# mcu.net
KiCad netlist of a schematic drawn in Altium Designer
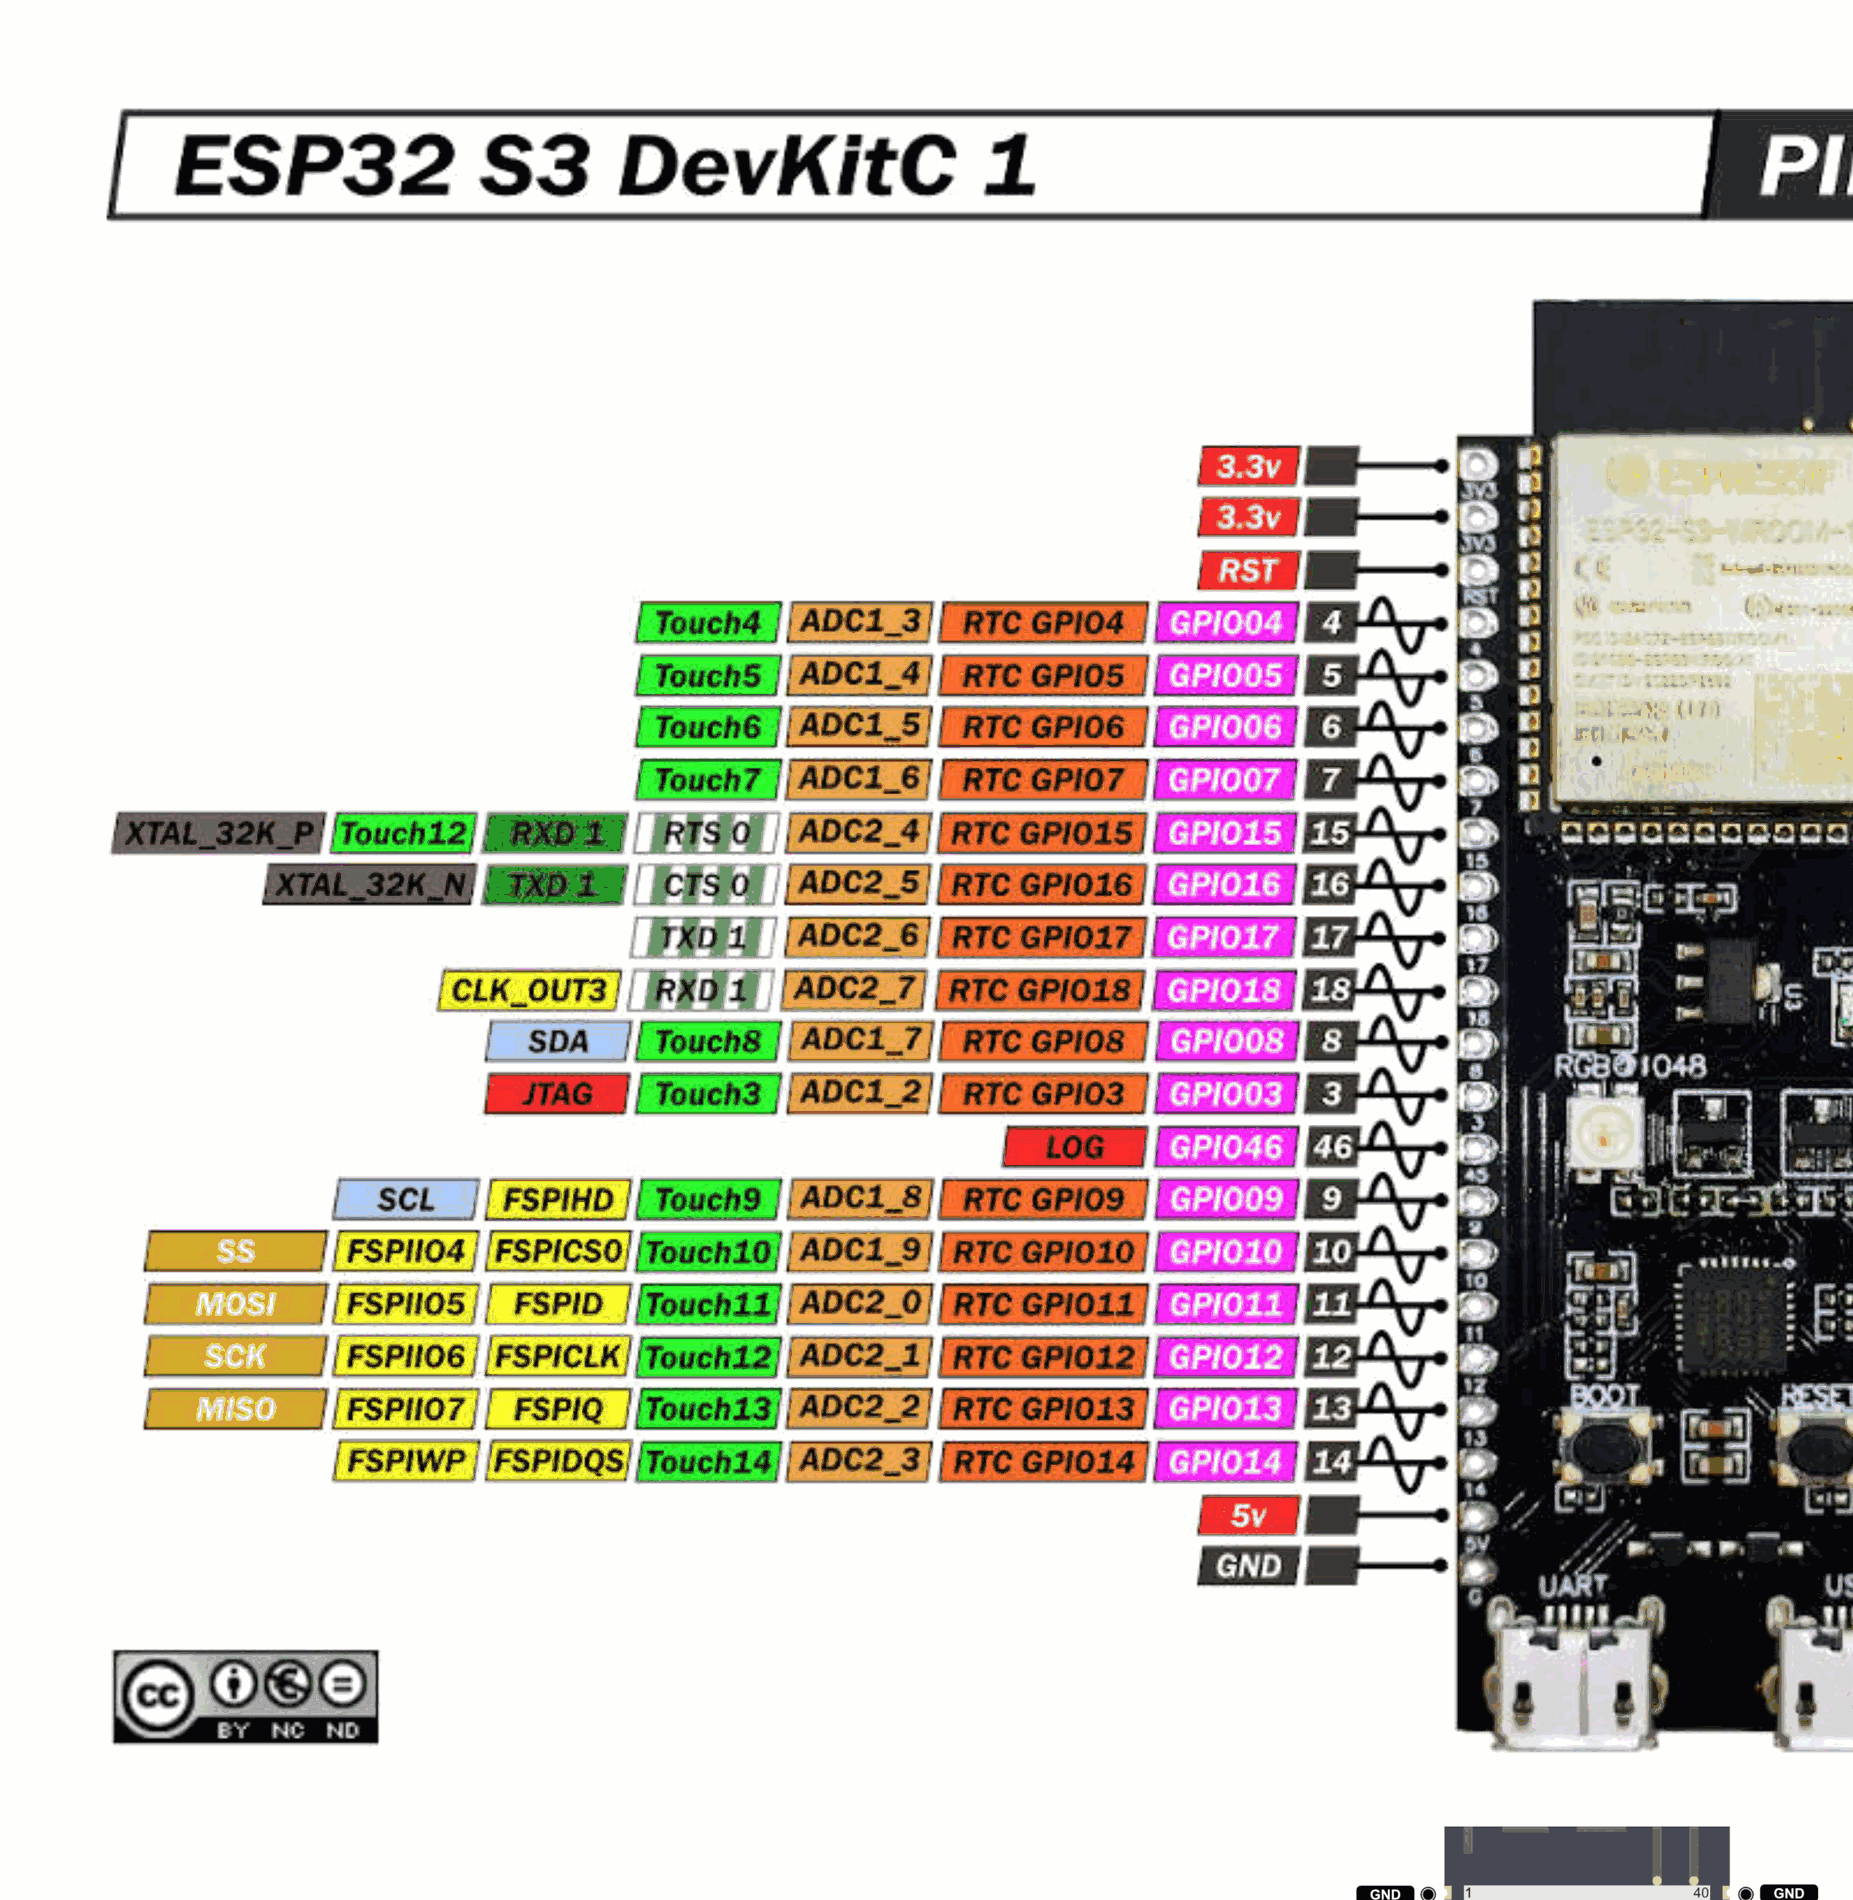
[diagram p0: mcu.SchDoc, top left]
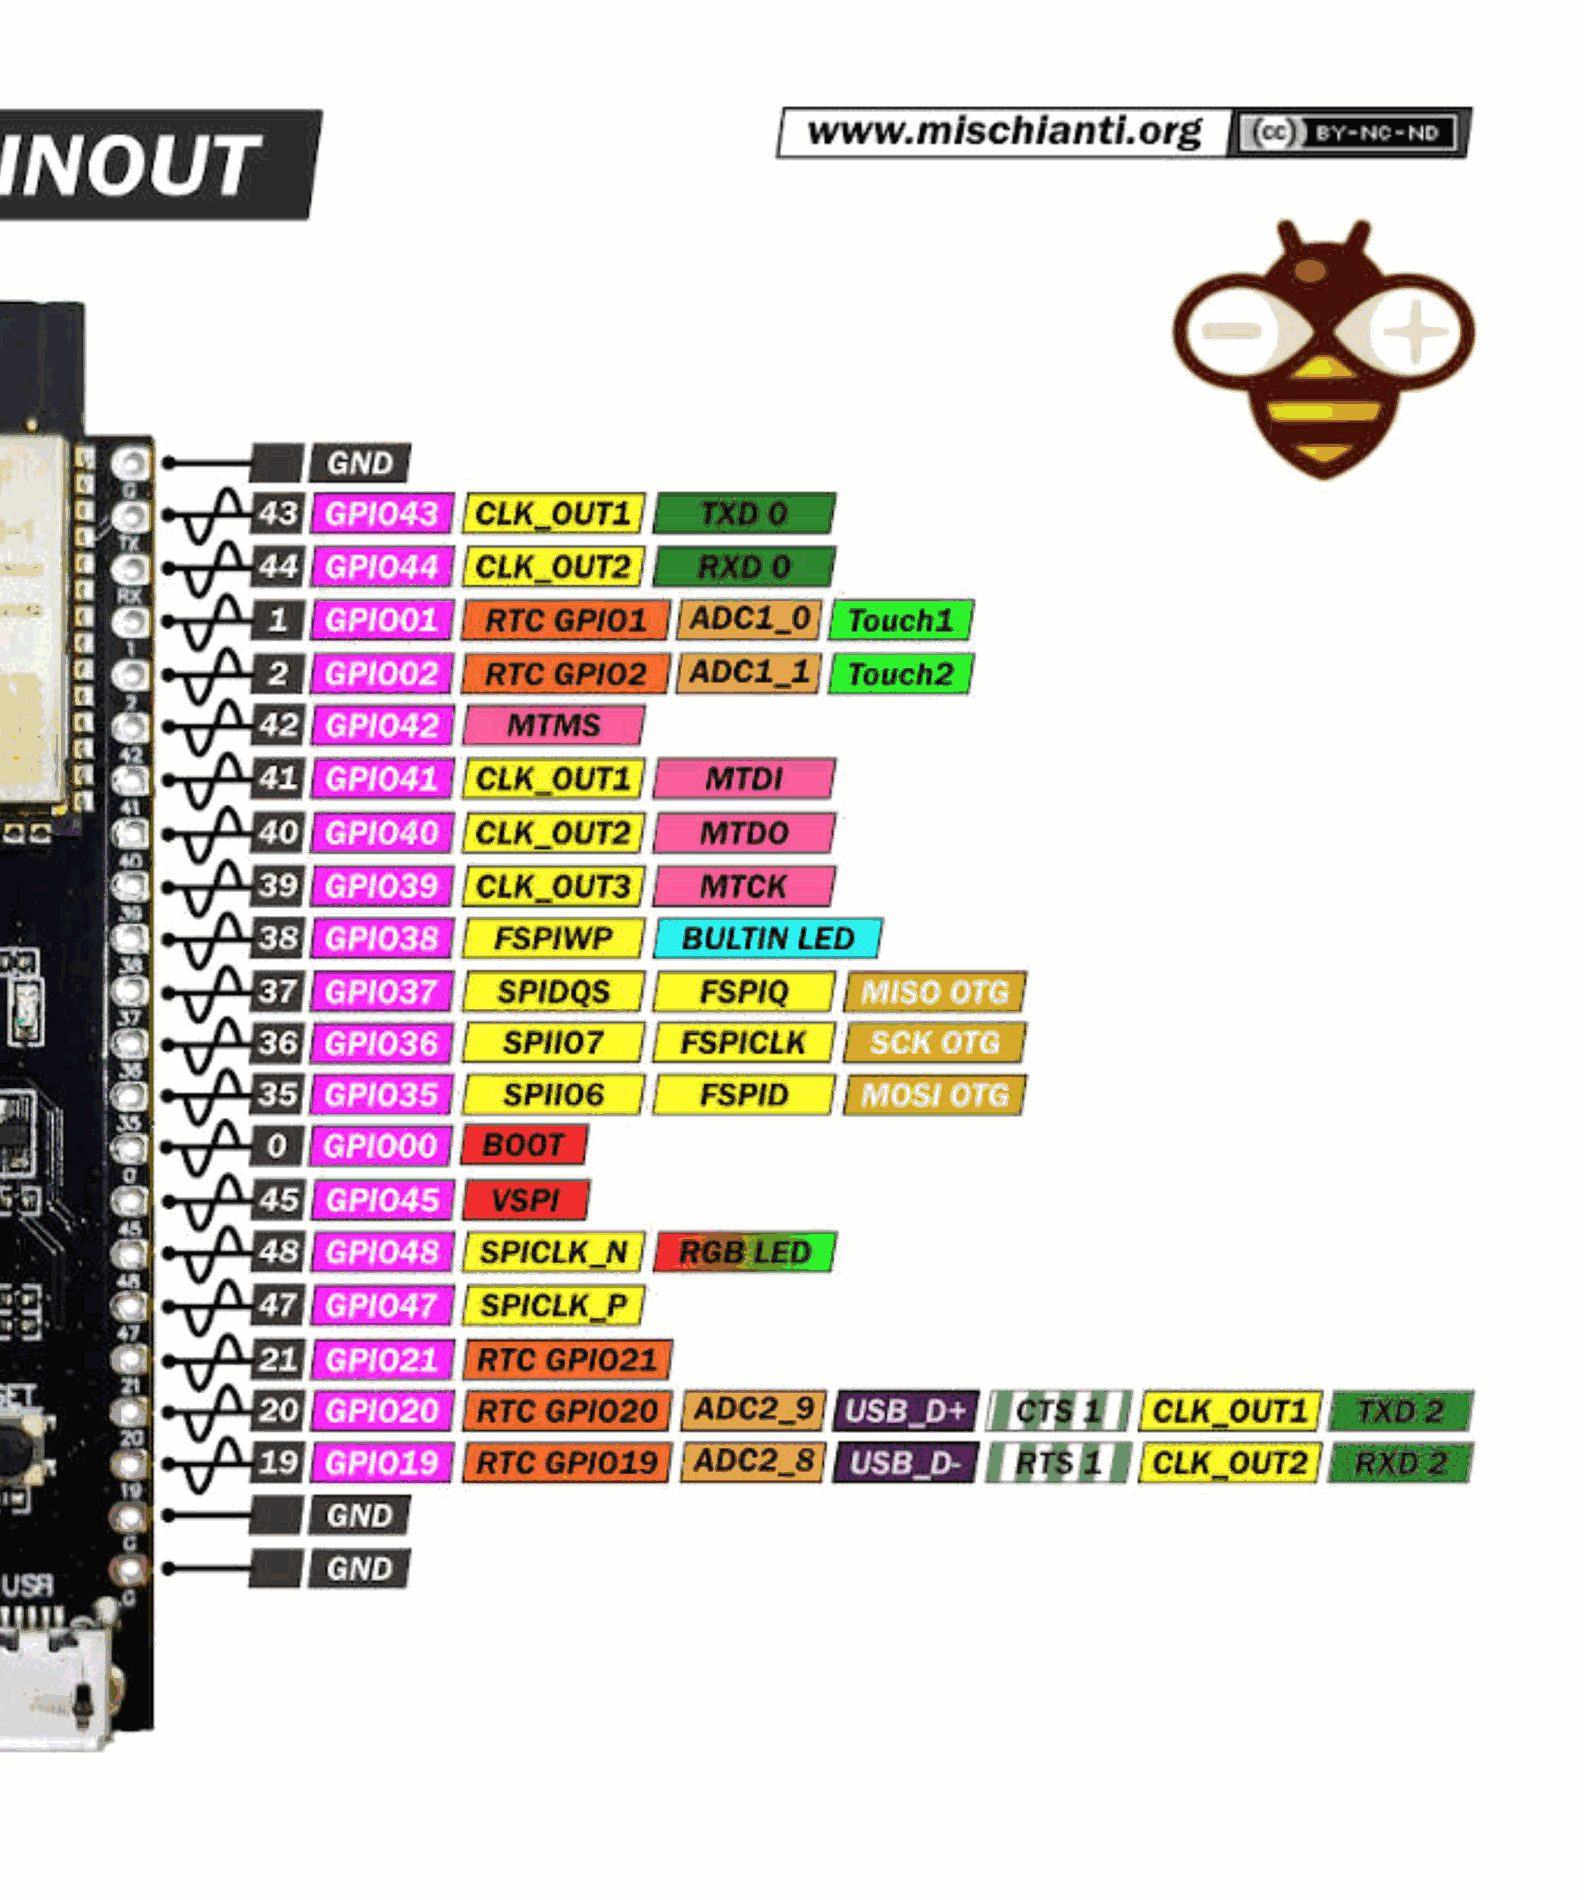
[diagram p1: mcu.SchDoc, top right]
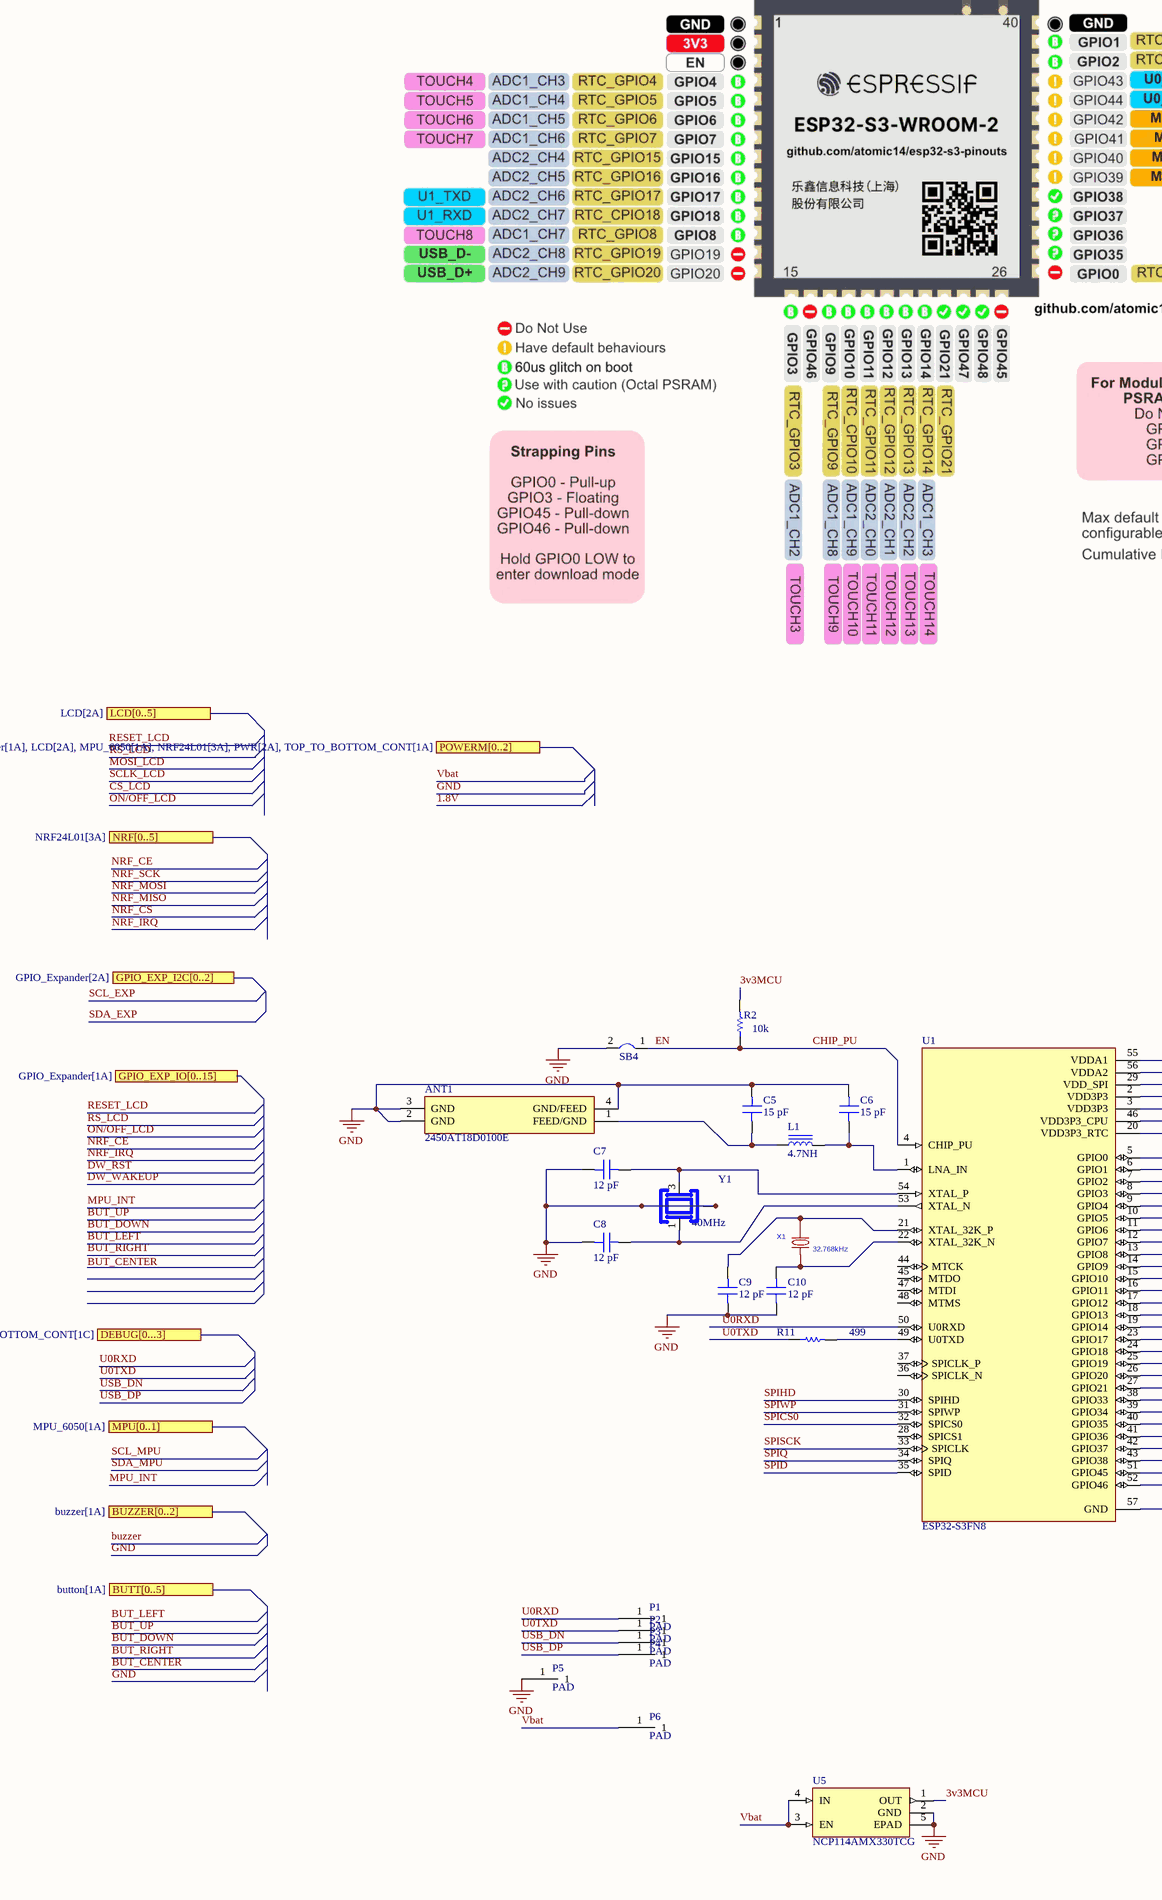
[diagram p2: mcu.SchDoc, bottom left]
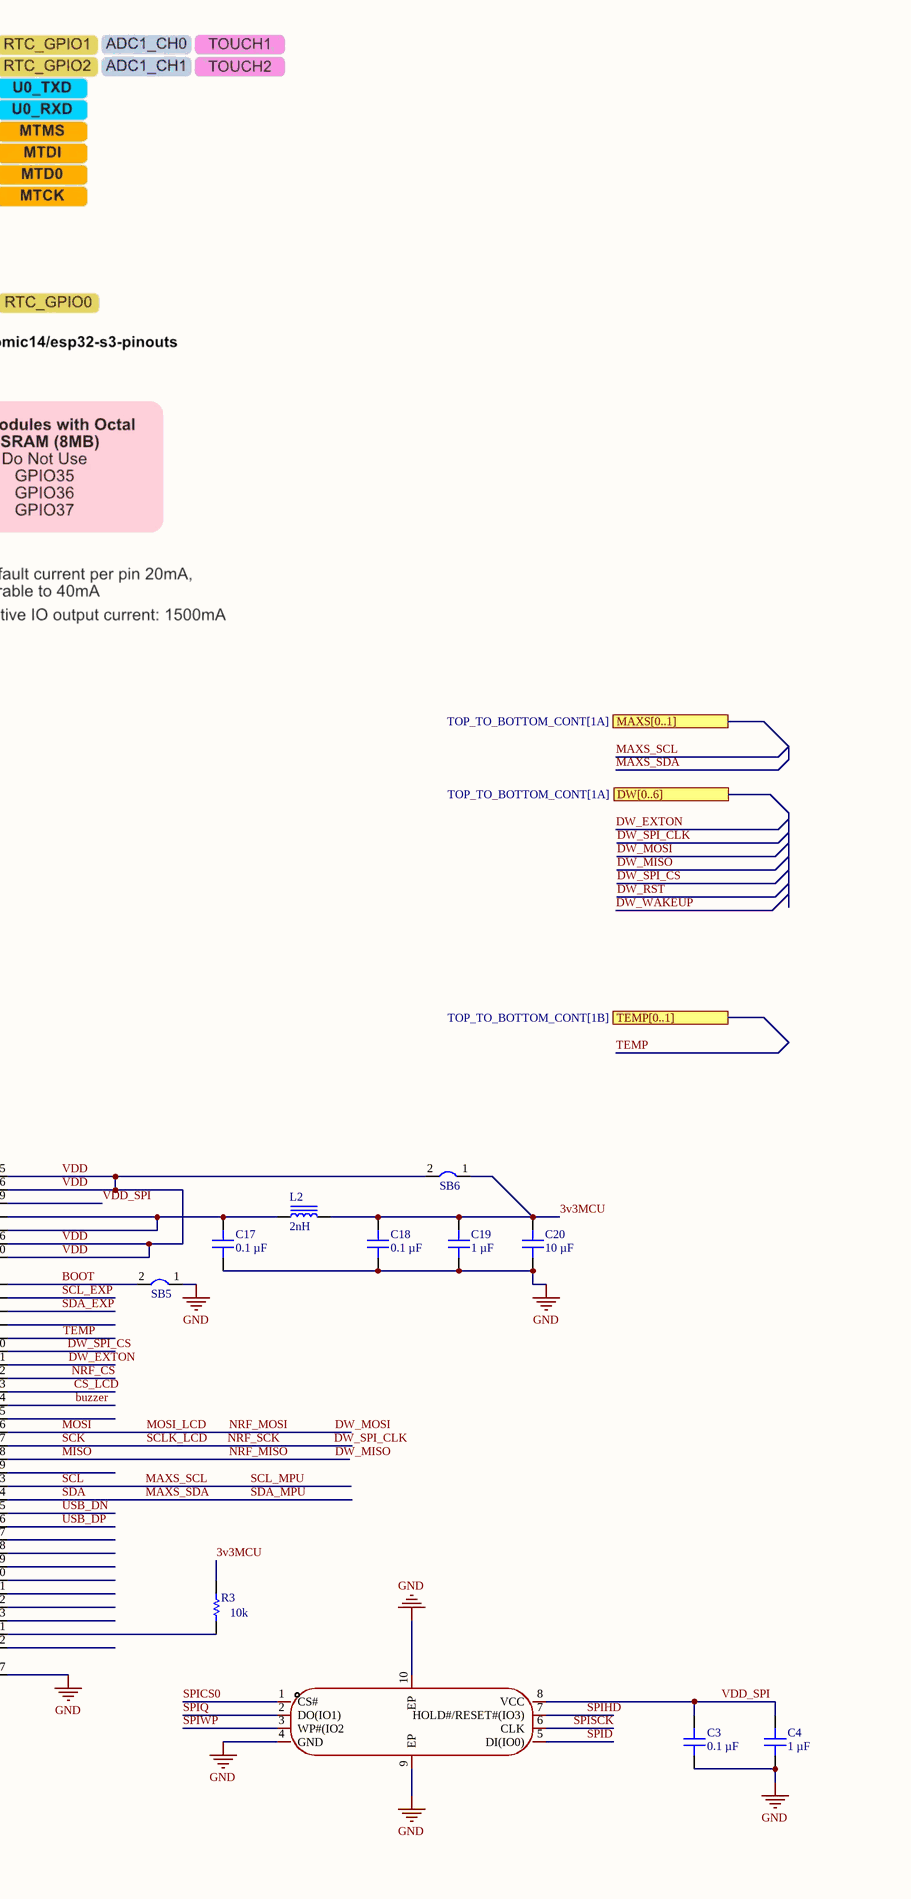
[diagram p3: mcu.SchDoc, bottom right]

(export (version "E")
  (design (tool "Eeschema 10.0.6"))
  (components
    (comp (ref "ANT1")
      (value "2450AT18D0100E")
      (footprint "FP-2450AT18D0100E-MFG")
      (description "RF ANT 2.4GHZ CHIP SOLDER SMD")
      (fields (field (name "JLCPCB PART #") "C2917718") (field (name "MANUFACTURER") "Johanson Dielectrics"))
      (libsource (lib "Altium Content Vault") (part "2754107183b9f3d7969499aeff111fc"))
    )
    (comp (ref "C3")
      (value "~")
      (footprint "CAP 0402_1005")
      (description "100nF 16V X7R ±10% 0402 Multilayer Ceramic Capacitors MLCC - SMD/SMT ROHS")
      (fields
        (field (name "CAPACITANCE") "0.1 µF")
        (field (name "MANUFACTURER") "YAGEO")
        (field (name "MFR.PART #") "CC0402KRX7R7BB104")
      )
      (libsource (lib "Celestial Altium Library - altium_library") (part "Capacitor"))
    )
    (comp (ref "C4")
      (value "~")
      (footprint "CAP 0402_1005")
      (description "10V 1uF X5R ±10% 0402 Multilayer Ceramic Capacitors MLCC - SMD/SMT ROHS")
      (fields
        (field (name "PART NUMBER") "CL05A105KP5NNNC")
        (field (name "CAPACITANCE") "1 µF")
        (field (name "MANUFACTURER") "Samsung Electro-Mechanics")
      )
      (libsource (lib "Celestial Altium Library - altium_library") (part "Capacitor"))
    )
    (comp (ref "C5")
      (value "~")
      (footprint "CAP 0402_1005")
      (description "CAP CER 15PF 200V C0G/NP0 0402")
      (fields
        (field (name "CAPACITANCE") "15 pF")
        (field (name "MANUFACTURER") "FH (Guangdong Fenghua Advanced Tech)")
        (field (name "MFR.PART #") "0402CG150J500NT")
      )
      (libsource (lib "Celestial Altium Library - altium_library") (part "Capacitor"))
    )
    (comp (ref "C6")
      (value "~")
      (footprint "CAP 0402_1005")
      (description "CAP CER 15PF 200V C0G/NP0 0402")
      (fields
        (field (name "CAPACITANCE") "15 pF")
        (field (name "MANUFACTURER") "FH (Guangdong Fenghua Advanced Tech)")
        (field (name "MFR.PART #") "0402CG150J500NT")
      )
      (libsource (lib "Celestial Altium Library - altium_library") (part "Capacitor"))
    )
    (comp (ref "C7")
      (value "~")
      (footprint "CAP 0402_1005")
      (description "CAP CER 12PF 200V C0G/NP0 0402")
      (fields
        (field (name "CAPACITANCE") "12 pF")
        (field (name "MANUFACTURER") "FH (Guangdong Fenghua Advanced Tech)")
        (field (name "MFR.PART #") "0402CG120J500NT")
      )
      (libsource (lib "Celestial Altium Library - altium_library") (part "Capacitor"))
    )
    (comp (ref "C8")
      (value "~")
      (footprint "CAP 0402_1005")
      (description "CAP CER 12PF 200V C0G/NP0 0402")
      (fields
        (field (name "CAPACITANCE") "12 pF")
        (field (name "MANUFACTURER") "FH (Guangdong Fenghua Advanced Tech)")
        (field (name "MFR.PART #") "0402CG120J500NT")
      )
      (libsource (lib "Celestial Altium Library - altium_library") (part "Capacitor"))
    )
    (comp (ref "C9")
      (value "~")
      (footprint "CAP 0402_1005")
      (description "CAP CER 12PF 200V C0G/NP0 0402")
      (fields
        (field (name "CAPACITANCE") "12 pF")
        (field (name "MANUFACTURER") "FH (Guangdong Fenghua Advanced Tech)")
        (field (name "MFR.PART #") "0402CG120J500NT")
      )
      (libsource (lib "Celestial Altium Library - altium_library") (part "Capacitor"))
    )
    (comp (ref "C10")
      (value "~")
      (footprint "CAP 0402_1005")
      (description "CAP CER 12PF 200V C0G/NP0 0402")
      (fields
        (field (name "PART NUMBER") "0402CG120J500NT")
        (field (name "CAPACITANCE") "12 pF")
        (field (name "MANUFACTURER") "FH (Guangdong Fenghua Advanced Tech)")
      )
      (libsource (lib "Celestial Altium Library - altium_library") (part "Capacitor"))
    )
    (comp (ref "C17")
      (value "~")
      (footprint "CAP 0402_1005")
      (description "100nF 16V X7R ±10% 0402 Multilayer Ceramic Capacitors MLCC - SMD/SMT ROHS")
      (fields
        (field (name "CAPACITANCE") "0.1 µF")
        (field (name "MANUFACTURER") "YAGEO")
        (field (name "MFR.PART #") "CC0402KRX7R7BB104")
      )
      (libsource (lib "Celestial Altium Library - altium_library") (part "Capacitor"))
    )
    (comp (ref "C18")
      (value "~")
      (footprint "CAP 0402_1005")
      (description "100nF 16V X7R ±10% 0402 Multilayer Ceramic Capacitors MLCC - SMD/SMT ROHS")
      (fields
        (field (name "CAPACITANCE") "0.1 µF")
        (field (name "MANUFACTURER") "YAGEO")
        (field (name "MFR.PART #") "CC0402KRX7R7BB104")
      )
      (libsource (lib "Celestial Altium Library - altium_library") (part "Capacitor"))
    )
    (comp (ref "C19")
      (value "~")
      (footprint "CAP 0402_1005")
      (description "10V 1uF X5R ±10% 0402 Multilayer Ceramic Capacitors MLCC - SMD/SMT ROHS")
      (fields
        (field (name "CAPACITANCE") "1 µF")
        (field (name "MANUFACTURER") "Samsung Electro-Mechanics")
        (field (name "MFR.PART #") "CL05A105KP5NNNC")
      )
      (libsource (lib "Celestial Altium Library - altium_library") (part "Capacitor"))
    )
    (comp (ref "C20")
      (value "~")
      (footprint "CAP 0402_1005")
      (description "10V 1uF X5R ±10% 0402 Multilayer Ceramic Capacitors MLCC - SMD/SMT ROHS")
      (fields
        (field (name "CAPACITANCE") "10 µF")
        (field (name "MANUFACTURER") "Samsung Electro-Mechanics")
        (field (name "MFR.PART #") "CL05A106MQ5NUNC")
      )
      (libsource (lib "Celestial Altium Library - altium_library") (part "Capacitor"))
    )
    (comp (ref "L1")
      (value "4.7NH")
      (footprint "Murata LQG15 0402")
      (description "200mΩ 300mA 4.7nH 4GHz 8@100MHz 0402 Inductors (SMD) ROHS")
      (fields (field (name "MANUFACTURER") "Sunlord") (field (name "MFR.PART #") "SDCL1005C4N7STDF"))
      (libsource (lib "Celestial Altium Library - altium_library") (part "Inductor"))
    )
    (comp (ref "L2")
      (value "2nH")
      (footprint "IND 0402_1005")
      (description "FIXED IND 2NH 596MA 180 MOHM SMD")
      (fields (field (name "PART NUMBER") "HLC022R0BTTR") (field (name "MANUFACTURER") "AVX Corporation"))
      (libsource (lib "Celestial Altium Library - altium_library") (part "Inductor"))
    )
    (comp (ref "P1") (value "PAD") (footprint "PCBComponent_1") (libsource (lib "PAD") (part "PAD")))
    (comp (ref "P2") (value "PAD") (footprint "PCBComponent_1") (libsource (lib "PAD") (part "PAD")))
    (comp (ref "P3") (value "PAD") (footprint "PCBComponent_1") (libsource (lib "PAD") (part "PAD")))
    (comp (ref "P4") (value "PAD") (footprint "PCBComponent_1") (libsource (lib "PAD") (part "PAD")))
    (comp (ref "P5") (value "PAD") (footprint "PCBComponent_1") (libsource (lib "PAD") (part "PAD")))
    (comp (ref "P6") (value "PAD") (footprint "PCBComponent_1") (libsource (lib "PAD") (part "PAD")))
    (comp (ref "R2")
      (value "0402WGF1002TCE")
      (footprint "RESC1005X40X25LL05T10")
      (fields
        (field (name "MANUFACTURER") "UNI-ROYAL(Uniroyal Elec)")
        (field (name "JLCPCB PART #") "C25744")
        (field (name "RESISTANCE") "10k")
      )
      (libsource (lib "Altium Content Vault") (part "RES"))
    )
    (comp (ref "R3")
      (value "0402WGF1002TCE")
      (footprint "RESC1005X40X25LL05T10")
      (fields
        (field (name "MANUFACTURER") "UNI-ROYAL(Uniroyal Elec)")
        (field (name "JLCPCB PART #") "C25744")
        (field (name "RESISTANCE") "10k")
      )
      (libsource (lib "Altium Content Vault") (part "RES"))
    )
    (comp (ref "R11")
      (value "TNPW0402499RBEED")
      (footprint "RESC1005X40X20LL05T10")
      (fields
        (field (name "MANUFACTURER") "YAGEO")
        (field (name "JLCPCB PART #") "C137970")
        (field (name "MFR.PART #") "RC0402FR-07499RL")
        (field (name "RESISTANCE") "499")
      )
      (libsource (lib "Altium Content Vault") (part "RES"))
    )
    (comp (ref "SB4")
      (value "Jumper")
      (footprint "Jumper")
      (libsource (lib "Integrated_Library2") (part "Jumper"))
    )
    (comp (ref "SB5")
      (value "Jumper")
      (footprint "Jumper")
      (libsource (lib "Integrated_Library2") (part "Jumper"))
    )
    (comp (ref "SB6")
      (value "Jumper")
      (footprint "Jumper")
      (libsource (lib "Integrated_Library2") (part "Jumper"))
    )
    (comp (ref "U1")
      (value "ESP32-S3FN8")
      (footprint "QFN40P700X700X90-57N")
      (fields (field (name "MANUFACTURER") "Espressif Systems") (field (name "JLCPCB PART #") "C2913196"))
      (libsource (lib "ESP32-S3FN8") (part "ESP32-S3FN8"))
    )
    (comp (ref "U3")
      (value "W25Q64JWUUIQ")
      (footprint "USON-8_L4.0-W3.0-P0.80-BL_WINBOND_UU")
      (fields (field (name "JLCPCB PART #") "C6604692") (field (name "MANUFACTURER") "Winbond Elec"))
      (libsource (lib "altium-import") (part "root_0_W25Q64JWUUIQ_"))
    )
    (comp (ref "U5")
      (value "NCP114AMX330TCG")
      (footprint "REG_NCP114AMX330TCG")
      (description "Linear Voltage Regulator IC Positive Fixed 1 Output 300mA 4-UDFN (1.0x1.0)")
      (fields (field (name "MANUFACTURER") "onsemi") (field (name "MFR.PART #") "C133056"))
      (libsource (lib "NCP114AMX330TCG") (part "NCP114AMX330TCG"))
    )
    (comp (ref "X1")
      (value "32.768kHz")
      (footprint "FC-135R_L3.2-W1.5")
      (fields
        (field (name "MANUFACTURER") "Seiko Epson")
        (field (name "MFR.PART #") "Q13FC13500004")
        (field (name "JLCPCB PART #") "C32346")
      )
      (libsource (lib "altium-import") (part "root_1_Q13FC13500004_C32346_"))
    )
    (comp (ref "Y1")
      (value "40MHz")
      (footprint "C5261125")
      (description "-40℃~+85℃ 12pF 40MHz Crystal Oscillator ±10ppm SMD2520-4P Crystals ROHS")
      (fields (field (name "MANUFACTURER") "Lucki") (field (name "JLCPCB PART #") "C5261125"))
      (libsource (lib "C5261125") (part "L225S400L11L"))
    )
  )
  (nets
    (net (code "58") (name "/3v3MCU") (class "Default")
      (node (ref "C18") (pin "2") (pinfunction "2_2") (pintype "passive"))
      (node (ref "C19") (pin "2") (pinfunction "2_2") (pintype "passive"))
      (node (ref "C20") (pin "2") (pinfunction "2_2") (pintype "passive"))
      (node (ref "L2") (pin "2") (pinfunction "2_2") (pintype "passive"))
      (node (ref "R2") (pin "2") (pinfunction "2_2") (pintype "passive"))
      (node (ref "R3") (pin "2") (pinfunction "2_2") (pintype "passive"))
      (node (ref "SB6") (pin "1") (pinfunction "1_1") (pintype "passive"))
      (node (ref "U5") (pin "1") (pinfunction "OUT_1") (pintype "output"))
    )
    (net (code "59") (name "/BOOT") (class "Default")
      (node (ref "SB5") (pin "2") (pinfunction "2_2") (pintype "passive"))
      (node (ref "U1") (pin "5") (pinfunction "GPIO0_5") (pintype "bidirectional"))
    )
    (net (code "67") (name "/CHIP_PU") (class "Default")
      (node (ref "R2") (pin "1") (pinfunction "1_1") (pintype "passive"))
      (node (ref "SB4") (pin "1") (pinfunction "1_1") (pintype "passive"))
      (node (ref "U1") (pin "4") (pinfunction "CHIP_PU_4") (pintype "input"))
    )
    (net (code "68") (name "/CS_LCD") (class "Default")
      (node (ref "U1") (pin "13") (pinfunction "GPIO8_13") (pintype "bidirectional"))
    )
    (net (code "71") (name "/DW_EXTON") (class "Default")
      (node (ref "U1") (pin "11") (pinfunction "GPIO6_11") (pintype "bidirectional"))
    )
    (net (code "72") (name "/DW_MISO") (class "Default")
      (node (ref "U1") (pin "18") (pinfunction "GPIO13_18") (pintype "bidirectional"))
    )
    (net (code "73") (name "/DW_MOSI") (class "Default")
      (node (ref "U1") (pin "16") (pinfunction "GPIO11_16") (pintype "bidirectional"))
    )
    (net (code "75") (name "/DW_SPI_CLK") (class "Default")
      (node (ref "U1") (pin "17") (pinfunction "GPIO12_17") (pintype "bidirectional"))
    )
    (net (code "76") (name "/DW_SPI_CS") (class "Default")
      (node (ref "U1") (pin "10") (pinfunction "GPIO5_10") (pintype "bidirectional"))
    )
    (net (code "82") (name "/MAXS_SCL") (class "Default")
      (node (ref "U1") (pin "23") (pinfunction "GPIO17_23") (pintype "bidirectional"))
    )
    (net (code "83") (name "/MAXS_SDA") (class "Default")
      (node (ref "U1") (pin "24") (pinfunction "GPIO18_24") (pintype "bidirectional"))
    )
    (net (code "88") (name "/NRF_CS") (class "Default")
      (node (ref "U1") (pin "12") (pinfunction "GPIO7_12") (pintype "bidirectional"))
    )
    (net (code "94") (name "/SCL_EXP") (class "Default")
      (node (ref "U1") (pin "6") (pinfunction "GPIO1_6") (pintype "bidirectional"))
    )
    (net (code "95") (name "/SDA_EXP") (class "Default")
      (node (ref "U1") (pin "7") (pinfunction "GPIO2_7") (pintype "bidirectional"))
    )
    (net (code "96") (name "/SPICS0") (class "Default")
      (node (ref "U1") (pin "32") (pinfunction "SPICS0_32") (pintype "bidirectional"))
      (node (ref "U3") (pin "1") (pinfunction "CS#_1") (pintype "passive"))
    )
    (net (code "97") (name "/SPID") (class "Default")
      (node (ref "U1") (pin "35") (pinfunction "SPID_35") (pintype "bidirectional"))
      (node (ref "U3") (pin "5") (pinfunction "DI(IO0)_5") (pintype "passive"))
    )
    (net (code "98") (name "/SPIHD") (class "Default")
      (node (ref "U1") (pin "30") (pinfunction "SPIHD_30") (pintype "bidirectional"))
      (node (ref "U3") (pin "7") (pinfunction "HOLD#/RESET#(IO3)_7") (pintype "passive"))
    )
    (net (code "99") (name "/SPIQ") (class "Default")
      (node (ref "U1") (pin "34") (pinfunction "SPIQ_34") (pintype "bidirectional"))
      (node (ref "U3") (pin "2") (pinfunction "DO(IO1)_2") (pintype "passive"))
    )
    (net (code "100") (name "/SPISCK") (class "Default")
      (node (ref "U1") (pin "33") (pinfunction "SPICLK_33") (pintype "bidirectional"))
      (node (ref "U3") (pin "6") (pinfunction "CLK_6") (pintype "passive"))
    )
    (net (code "101") (name "/SPIWP") (class "Default")
      (node (ref "U1") (pin "31") (pinfunction "SPIWP_31") (pintype "bidirectional"))
      (node (ref "U3") (pin "3") (pinfunction "WP#(IO2_3") (pintype "passive"))
    )
    (net (code "102") (name "/TEMP") (class "Default")
      (node (ref "U1") (pin "9") (pinfunction "GPIO4_9") (pintype "bidirectional"))
    )
    (net (code "104") (name "/U0RXD") (class "Default")
      (node (ref "P1") (pin "1") (pinfunction "1_1") (pintype "passive"))
      (node (ref "U1") (pin "50") (pinfunction "U0RXD_50") (pintype "bidirectional"))
    )
    (net (code "105") (name "/U0TXD") (class "Default")
      (node (ref "P2") (pin "1") (pinfunction "1_1") (pintype "passive"))
      (node (ref "R11") (pin "1") (pinfunction "1_1") (pintype "passive"))
    )
    (net (code "106") (name "/USB_DN") (class "Default")
      (node (ref "P3") (pin "1") (pinfunction "1_1") (pintype "passive"))
      (node (ref "U1") (pin "25") (pinfunction "GPIO19_25") (pintype "bidirectional"))
    )
    (net (code "107") (name "/USB_DP") (class "Default")
      (node (ref "P4") (pin "1") (pinfunction "1_1") (pintype "passive"))
      (node (ref "U1") (pin "26") (pinfunction "GPIO20_26") (pintype "bidirectional"))
    )
    (net (code "108") (name "/VDD") (class "Default")
      (node (ref "SB6") (pin "2") (pinfunction "2_2") (pintype "passive"))
      (node (ref "U1") (pin "20") (pinfunction "VDD3P3_RTC_20") (pintype "power_in"))
      (node (ref "U1") (pin "46") (pinfunction "VDD3P3_CPU_46") (pintype "power_in"))
      (node (ref "U1") (pin "55") (pinfunction "VDDA1_55") (pintype "power_in"))
      (node (ref "U1") (pin "56") (pinfunction "VDDA2_56") (pintype "power_in"))
    )
    (net (code "109") (name "/VDD_SPI") (class "Default")
      (node (ref "C3") (pin "2") (pinfunction "2_2") (pintype "passive"))
      (node (ref "C4") (pin "2") (pinfunction "2_2") (pintype "passive"))
      (node (ref "U1") (pin "29") (pinfunction "VDD_SPI_29") (pintype "power_in"))
      (node (ref "U3") (pin "8") (pinfunction "VCC_8") (pintype "passive"))
    )
    (net (code "110") (name "/Vbat") (class "Default")
      (node (ref "P6") (pin "1") (pinfunction "1_1") (pintype "passive"))
      (node (ref "U5") (pin "3") (pinfunction "EN_3") (pintype "input"))
      (node (ref "U5") (pin "4") (pinfunction "IN_4") (pintype "input"))
    )
    (net (code "111") (name "/buzzer") (class "Default")
      (node (ref "U1") (pin "14") (pinfunction "GPIO9_14") (pintype "bidirectional"))
    )
    (net (code "112") (name "GND") (class "Default")
      (node (ref "ANT1") (pin "2") (pinfunction "GND_2") (pintype "power_in"))
      (node (ref "ANT1") (pin "3") (pinfunction "GND_3") (pintype "power_in"))
      (node (ref "ANT1") (pin "4") (pinfunction "GND/FEED_4") (pintype "power_in"))
      (node (ref "C10") (pin "2") (pinfunction "2_2") (pintype "passive"))
      (node (ref "C17") (pin "1") (pinfunction "1_1") (pintype "passive"))
      (node (ref "C18") (pin "1") (pinfunction "1_1") (pintype "passive"))
      (node (ref "C19") (pin "1") (pinfunction "1_1") (pintype "passive"))
      (node (ref "C20") (pin "1") (pinfunction "1_1") (pintype "passive"))
      (node (ref "C3") (pin "1") (pinfunction "1_1") (pintype "passive"))
      (node (ref "C4") (pin "1") (pinfunction "1_1") (pintype "passive"))
      (node (ref "C5") (pin "2") (pinfunction "2_2") (pintype "passive"))
      (node (ref "C6") (pin "2") (pinfunction "2_2") (pintype "passive"))
      (node (ref "C7") (pin "1") (pinfunction "1_1") (pintype "passive"))
      (node (ref "C8") (pin "1") (pinfunction "1_1") (pintype "passive"))
      (node (ref "C9") (pin "2") (pinfunction "2_2") (pintype "passive"))
      (node (ref "P5") (pin "1") (pinfunction "1_1") (pintype "passive"))
      (node (ref "SB4") (pin "2") (pinfunction "2_2") (pintype "passive"))
      (node (ref "SB5") (pin "1") (pinfunction "1_1") (pintype "passive"))
      (node (ref "U1") (pin "57") (pinfunction "GND_57") (pintype "power_in"))
      (node (ref "U3") (pin "10") (pinfunction "EP_10") (pintype "passive"))
      (node (ref "U3") (pin "4") (pinfunction "GND_4") (pintype "passive"))
      (node (ref "U3") (pin "9") (pinfunction "EP_9") (pintype "passive"))
      (node (ref "U5") (pin "2") (pinfunction "GND_2") (pintype "power_in"))
      (node (ref "U5") (pin "5") (pinfunction "EPAD_5") (pintype "passive"))
      (node (ref "Y1") (pin "2") (pinfunction "GND_2") (pintype "power_in"))
      (node (ref "Y1") (pin "4") (pinfunction "GND_4") (pintype "power_in"))
    )
    (net (code "113") (name "Net-(ANT1-FEED{slash}GND)") (class "Default")
      (node (ref "ANT1") (pin "1") (pinfunction "FEED/GND_1") (pintype "power_in"))
      (node (ref "C5") (pin "1") (pinfunction "1_1") (pintype "passive"))
      (node (ref "L1") (pin "1") (pinfunction "1_1") (pintype "passive"))
    )
    (net (code "114") (name "Net-(C17-Pad2)") (class "Default")
      (node (ref "C17") (pin "2") (pinfunction "2_2") (pintype "passive"))
      (node (ref "L2") (pin "1") (pinfunction "1_1") (pintype "passive"))
      (node (ref "U1") (pin "2") (pinfunction "VDD3P3_2") (pintype "power_in"))
      (node (ref "U1") (pin "3") (pinfunction "VDD3P3_3") (pintype "power_in"))
    )
    (net (code "115") (name "Net-(U1-GPIO45)") (class "Default")
      (node (ref "R3") (pin "1") (pinfunction "1_1") (pintype "passive"))
      (node (ref "U1") (pin "51") (pinfunction "GPIO45_51") (pintype "bidirectional"))
    )
    (net (code "116") (name "Net-(U1-LNA_IN)") (class "Default")
      (node (ref "C6") (pin "1") (pinfunction "1_1") (pintype "passive"))
      (node (ref "L1") (pin "2") (pinfunction "2_2") (pintype "passive"))
      (node (ref "U1") (pin "1") (pinfunction "LNA_IN_1") (pintype "bidirectional"))
    )
    (net (code "117") (name "Net-(U1-U0TXD)") (class "Default")
      (node (ref "R11") (pin "2") (pinfunction "2_2") (pintype "passive"))
      (node (ref "U1") (pin "49") (pinfunction "U0TXD_49") (pintype "bidirectional"))
    )
    (net (code "118") (name "Net-(U1-XTAL_32K_N)") (class "Default")
      (node (ref "C10") (pin "1") (pinfunction "1_1") (pintype "passive"))
      (node (ref "U1") (pin "22") (pinfunction "XTAL_32K_N_22") (pintype "bidirectional"))
      (node (ref "X1") (pin "1") (pinfunction "1_1") (pintype "passive"))
    )
    (net (code "119") (name "Net-(U1-XTAL_32K_P)") (class "Default")
      (node (ref "C9") (pin "1") (pinfunction "1_1") (pintype "passive"))
      (node (ref "U1") (pin "21") (pinfunction "XTAL_32K_P_21") (pintype "bidirectional"))
      (node (ref "X1") (pin "2") (pinfunction "2_2") (pintype "passive"))
    )
    (net (code "120") (name "Net-(U1-XTAL_N)") (class "Default")
      (node (ref "C8") (pin "2") (pinfunction "2_2") (pintype "passive"))
      (node (ref "U1") (pin "53") (pinfunction "XTAL_N_53") (pintype "output"))
      (node (ref "Y1") (pin "1") (pinfunction "IN/OUT_1") (pintype "passive"))
    )
    (net (code "121") (name "Net-(U1-XTAL_P)") (class "Default")
      (node (ref "C7") (pin "2") (pinfunction "2_2") (pintype "passive"))
      (node (ref "U1") (pin "54") (pinfunction "XTAL_P_54") (pintype "input"))
      (node (ref "Y1") (pin "3") (pinfunction "OUT/IN_3") (pintype "passive"))
    )
    (net (code "122") (name "unconnected-(U1-GPIO3-Pad8)") (class "Default")
      (node (ref "U1") (pin "8") (pinfunction "GPIO3_8") (pintype "bidirectional"))
    )
    (net (code "123") (name "unconnected-(U1-GPIO10-Pad15)") (class "Default")
      (node (ref "U1") (pin "15") (pinfunction "GPIO10_15") (pintype "bidirectional"))
    )
    (net (code "124") (name "unconnected-(U1-GPIO14-Pad19)") (class "Default")
      (node (ref "U1") (pin "19") (pinfunction "GPIO14_19") (pintype "bidirectional"))
    )
    (net (code "125") (name "unconnected-(U1-GPIO21-Pad27)") (class "Default")
      (node (ref "U1") (pin "27") (pinfunction "GPIO21_27") (pintype "bidirectional"))
    )
    (net (code "126") (name "unconnected-(U1-GPIO33-Pad38)") (class "Default")
      (node (ref "U1") (pin "38") (pinfunction "GPIO33_38") (pintype "bidirectional"))
    )
    (net (code "127") (name "unconnected-(U1-GPIO34-Pad39)") (class "Default")
      (node (ref "U1") (pin "39") (pinfunction "GPIO34_39") (pintype "bidirectional"))
    )
    (net (code "128") (name "unconnected-(U1-GPIO35-Pad40)") (class "Default")
      (node (ref "U1") (pin "40") (pinfunction "GPIO35_40") (pintype "bidirectional"))
    )
    (net (code "129") (name "unconnected-(U1-GPIO36-Pad41)") (class "Default")
      (node (ref "U1") (pin "41") (pinfunction "GPIO36_41") (pintype "bidirectional"))
    )
    (net (code "130") (name "unconnected-(U1-GPIO37-Pad42)") (class "Default")
      (node (ref "U1") (pin "42") (pinfunction "GPIO37_42") (pintype "bidirectional"))
    )
    (net (code "131") (name "unconnected-(U1-GPIO38-Pad43)") (class "Default")
      (node (ref "U1") (pin "43") (pinfunction "GPIO38_43") (pintype "bidirectional"))
    )
    (net (code "132") (name "unconnected-(U1-GPIO46-Pad52)") (class "Default")
      (node (ref "U1") (pin "52") (pinfunction "GPIO46_52") (pintype "bidirectional"))
    )
    (net (code "133") (name "unconnected-(U1-MTCK-Pad44)") (class "Default")
      (node (ref "U1") (pin "44") (pinfunction "MTCK_44") (pintype "bidirectional"))
    )
    (net (code "134") (name "unconnected-(U1-MTDI-Pad47)") (class "Default")
      (node (ref "U1") (pin "47") (pinfunction "MTDI_47") (pintype "bidirectional"))
    )
    (net (code "135") (name "unconnected-(U1-MTDO-Pad45)") (class "Default")
      (node (ref "U1") (pin "45") (pinfunction "MTDO_45") (pintype "bidirectional"))
    )
    (net (code "136") (name "unconnected-(U1-MTMS-Pad48)") (class "Default")
      (node (ref "U1") (pin "48") (pinfunction "MTMS_48") (pintype "bidirectional"))
    )
    (net (code "137") (name "unconnected-(U1-SPICLK_N-Pad36)") (class "Default")
      (node (ref "U1") (pin "36") (pinfunction "SPICLK_N_36") (pintype "bidirectional"))
    )
    (net (code "138") (name "unconnected-(U1-SPICLK_P-Pad37)") (class "Default")
      (node (ref "U1") (pin "37") (pinfunction "SPICLK_P_37") (pintype "bidirectional"))
    )
    (net (code "139") (name "unconnected-(U1-SPICS1-Pad28)") (class "Default")
      (node (ref "U1") (pin "28") (pinfunction "SPICS1_28") (pintype "bidirectional"))
    )
  )
)
